# Daughter_Board_V2.net
KiCad netlist of a schematic drawn in EAGLE
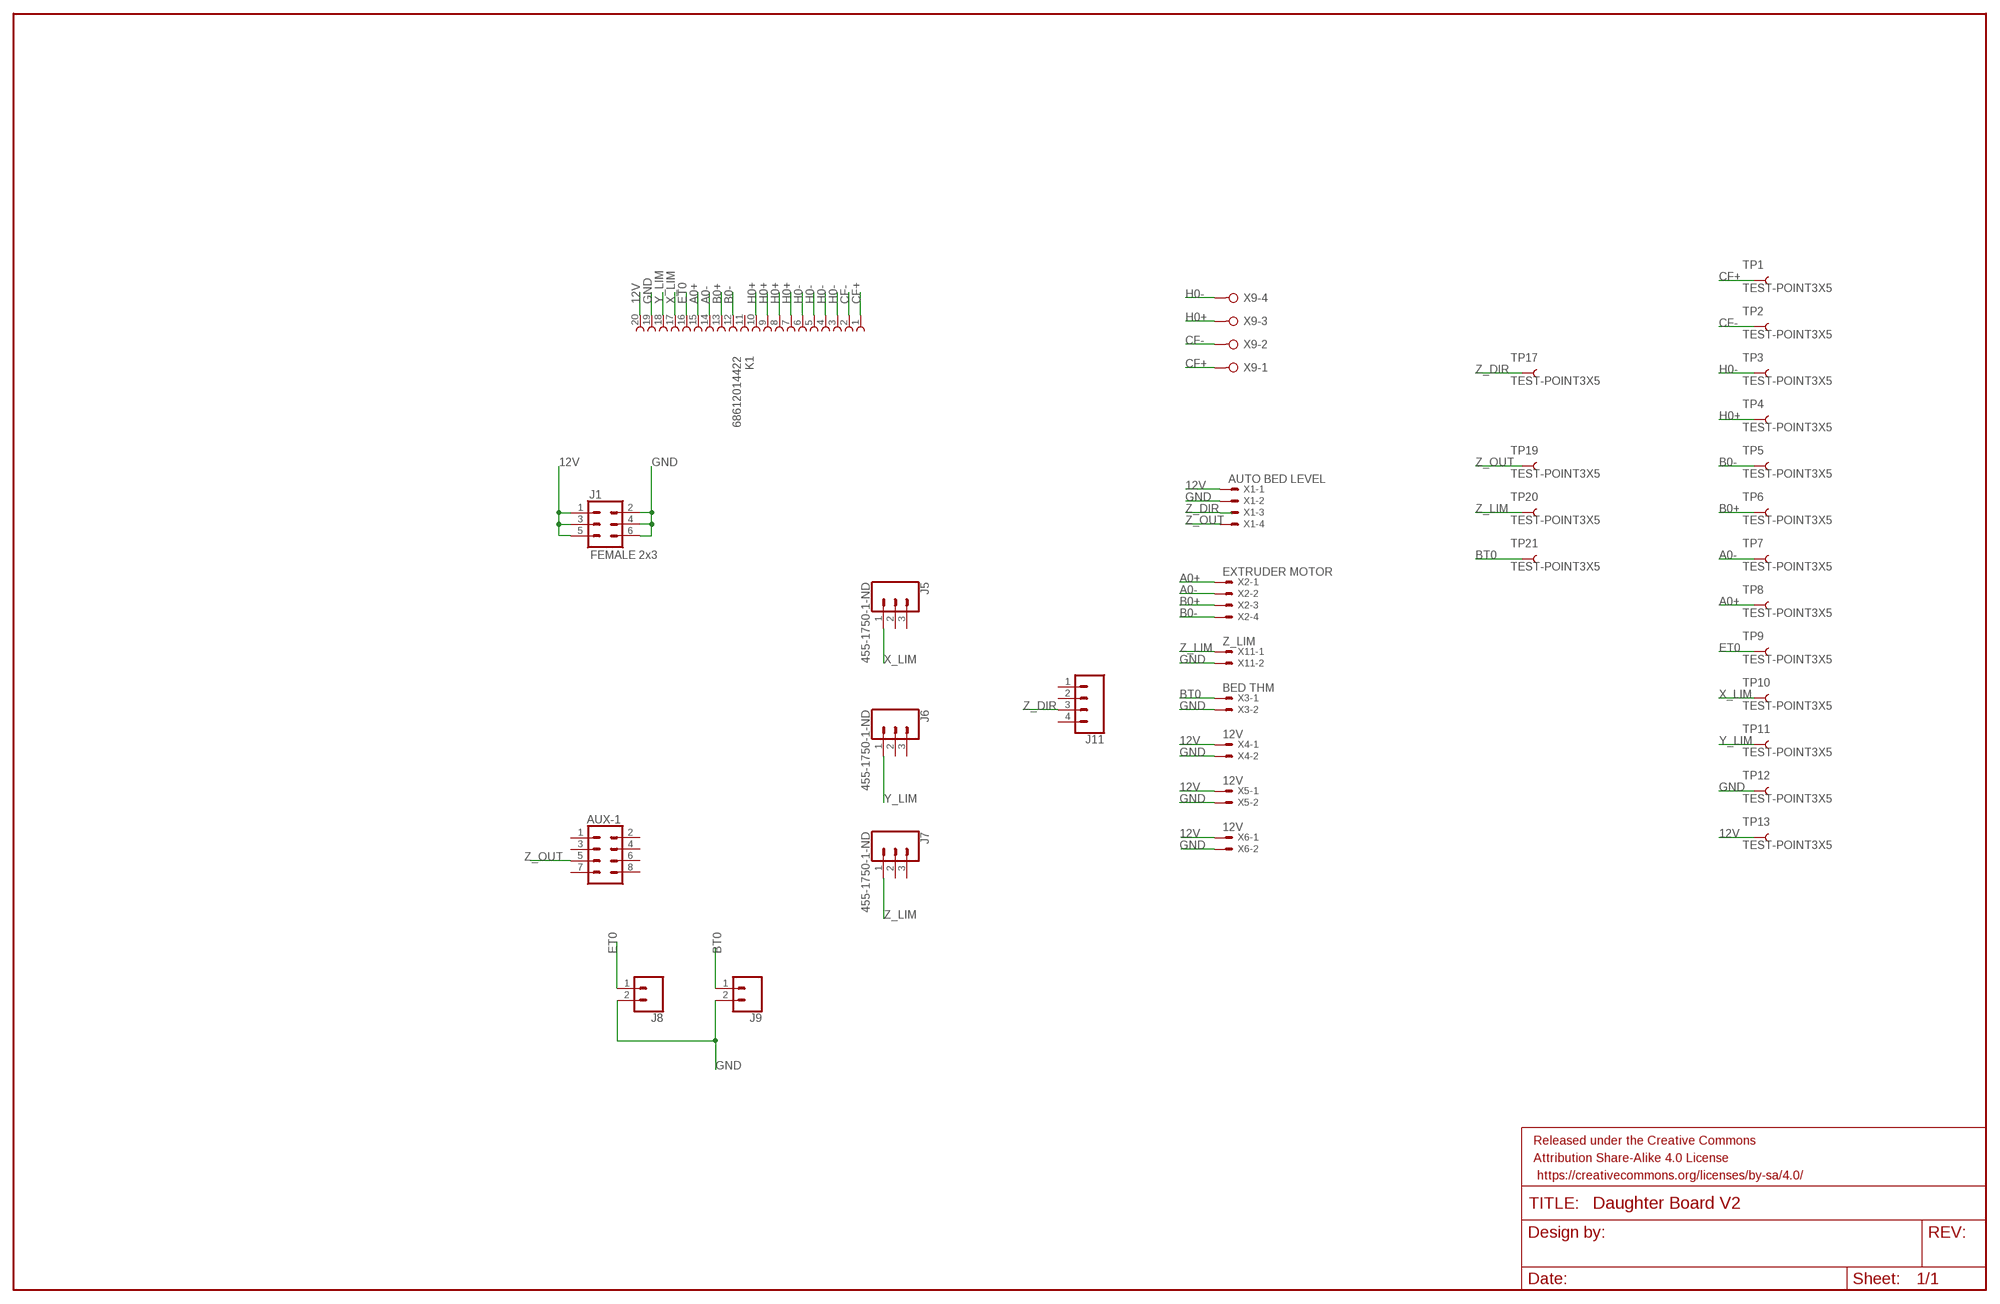
[diagram p0: schematic, sheet 1]

(export (version "E")
  (design (tool "Eeschema 10.0.6"))
  (components
    (comp (ref "AUX-1")
      (value "CONN_04X2")
      (footprint "eagle-import:2X4")
      (libsource (lib "eagle-import") (part "CONN_04X2"))
    )
    (comp (ref "FRAME1")
      (value "FRAME-LEDGER")
      (footprint "eagle-import:CREATIVE_COMMONS")
      (libsource (lib "eagle-import") (part "FRAME-LEDGER"))
    )
    (comp (ref "J1")
      (value "FEMALE 2x3")
      (footprint "eagle-import:2X3")
      (libsource (lib "eagle-import") (part "CONN_03X2FEMALE"))
    )
    (comp (ref "J5")
      (value "455-1750-1-ND")
      (footprint "eagle-import:1X03")
      (libsource (lib "eagle-import") (part "CONN_03"))
    )
    (comp (ref "J6")
      (value "455-1750-1-ND")
      (footprint "eagle-import:1X03")
      (libsource (lib "eagle-import") (part "CONN_03"))
    )
    (comp (ref "J7")
      (value "455-1750-1-ND")
      (footprint "eagle-import:1X03")
      (libsource (lib "eagle-import") (part "CONN_03"))
    )
    (comp (ref "J8")
      (value "CONN_02")
      (footprint "eagle-import:1X02")
      (libsource (lib "eagle-import") (part "CONN_02"))
    )
    (comp (ref "J9")
      (value "CONN_02")
      (footprint "eagle-import:1X02")
      (libsource (lib "eagle-import") (part "CONN_02"))
    )
    (comp (ref "J11")
      (value "CONN_04")
      (footprint "eagle-import:1X04")
      (libsource (lib "eagle-import") (part "CONN_04"))
    )
    (comp (ref "K1")
      (value "68612014422")
      (footprint "eagle-import:68612014422")
      (libsource (lib "eagle-import") (part "68612014422"))
    )
    (comp (ref "TP1")
      (value "TEST-POINT3X5")
      (footprint "eagle-import:PAD.03X.05")
      (libsource (lib "eagle-import") (part "TEST-POINT3X5"))
    )
    (comp (ref "TP2")
      (value "TEST-POINT3X5")
      (footprint "eagle-import:PAD.03X.05")
      (libsource (lib "eagle-import") (part "TEST-POINT3X5"))
    )
    (comp (ref "TP3")
      (value "TEST-POINT3X5")
      (footprint "eagle-import:PAD.03X.05")
      (libsource (lib "eagle-import") (part "TEST-POINT3X5"))
    )
    (comp (ref "TP4")
      (value "TEST-POINT3X5")
      (footprint "eagle-import:PAD.03X.05")
      (libsource (lib "eagle-import") (part "TEST-POINT3X5"))
    )
    (comp (ref "TP5")
      (value "TEST-POINT3X5")
      (footprint "eagle-import:PAD.03X.05")
      (libsource (lib "eagle-import") (part "TEST-POINT3X5"))
    )
    (comp (ref "TP6")
      (value "TEST-POINT3X5")
      (footprint "eagle-import:PAD.03X.05")
      (libsource (lib "eagle-import") (part "TEST-POINT3X5"))
    )
    (comp (ref "TP7")
      (value "TEST-POINT3X5")
      (footprint "eagle-import:PAD.03X.05")
      (libsource (lib "eagle-import") (part "TEST-POINT3X5"))
    )
    (comp (ref "TP8")
      (value "TEST-POINT3X5")
      (footprint "eagle-import:PAD.03X.05")
      (libsource (lib "eagle-import") (part "TEST-POINT3X5"))
    )
    (comp (ref "TP9")
      (value "TEST-POINT3X5")
      (footprint "eagle-import:PAD.03X.05")
      (libsource (lib "eagle-import") (part "TEST-POINT3X5"))
    )
    (comp (ref "TP10")
      (value "TEST-POINT3X5")
      (footprint "eagle-import:PAD.03X.05")
      (libsource (lib "eagle-import") (part "TEST-POINT3X5"))
    )
    (comp (ref "TP11")
      (value "TEST-POINT3X5")
      (footprint "eagle-import:PAD.03X.05")
      (libsource (lib "eagle-import") (part "TEST-POINT3X5"))
    )
    (comp (ref "TP12")
      (value "TEST-POINT3X5")
      (footprint "eagle-import:PAD.03X.05")
      (libsource (lib "eagle-import") (part "TEST-POINT3X5"))
    )
    (comp (ref "TP13")
      (value "TEST-POINT3X5")
      (footprint "eagle-import:PAD.03X.05")
      (libsource (lib "eagle-import") (part "TEST-POINT3X5"))
    )
    (comp (ref "TP17")
      (value "TEST-POINT3X5")
      (footprint "eagle-import:PAD.03X.05")
      (libsource (lib "eagle-import") (part "TEST-POINT3X5"))
    )
    (comp (ref "TP19")
      (value "TEST-POINT3X5")
      (footprint "eagle-import:PAD.03X.05")
      (libsource (lib "eagle-import") (part "TEST-POINT3X5"))
    )
    (comp (ref "TP20")
      (value "TEST-POINT3X5")
      (footprint "eagle-import:PAD.03X.05")
      (libsource (lib "eagle-import") (part "TEST-POINT3X5"))
    )
    (comp (ref "TP21")
      (value "TEST-POINT3X5")
      (footprint "eagle-import:PAD.03X.05")
      (libsource (lib "eagle-import") (part "TEST-POINT3X5"))
    )
    (comp (ref "X1")
      (value "AUTO BED LEVEL")
      (footprint "eagle-import:JST-XH-04-PACKAGE-LONG-PAD")
      (libsource (lib "eagle-import") (part "JST-XH-04-PIN-LONG-PAD"))
    )
    (comp (ref "X2")
      (value "EXTRUDER MOTOR")
      (footprint "eagle-import:JST-XH-04-PACKAGE-LONG-PAD")
      (libsource (lib "eagle-import") (part "JST-XH-04-PIN-LONG-PAD"))
    )
    (comp (ref "X3")
      (value "BED THM")
      (footprint "eagle-import:JST-XH-02-PACKAGE-LONG-PAD")
      (libsource (lib "eagle-import") (part "JST-XH-02-PIN-LONG-PAD"))
    )
    (comp (ref "X4")
      (value "12V")
      (footprint "eagle-import:JST-XH-02-PACKAGE-LONG-PAD")
      (libsource (lib "eagle-import") (part "JST-XH-02-PIN-LONG-PAD"))
    )
    (comp (ref "X5")
      (value "12V")
      (footprint "eagle-import:JST-XH-02-PACKAGE-LONG-PAD")
      (libsource (lib "eagle-import") (part "JST-XH-02-PIN-LONG-PAD"))
    )
    (comp (ref "X6")
      (value "12V")
      (footprint "eagle-import:JST-XH-02-PACKAGE-LONG-PAD")
      (libsource (lib "eagle-import") (part "JST-XH-02-PIN-LONG-PAD"))
    )
    (comp (ref "X9")
      (value "W237-04P")
      (footprint "eagle-import:W237-4P")
      (libsource (lib "eagle-import") (part "W237-04P"))
    )
    (comp (ref "X11")
      (value "Z_LIM")
      (footprint "eagle-import:JST-XH-02-PACKAGE-LONG-PAD")
      (libsource (lib "eagle-import") (part "JST-XH-02-PIN-LONG-PAD"))
    )
  )
  (nets
    (net (code "1") (name "/12V") (class "Default")
      (node (ref "J1") (pin "1") (pinfunction "1_1") (pintype "bidirectional"))
      (node (ref "J1") (pin "3") (pinfunction "3_3") (pintype "bidirectional"))
      (node (ref "J1") (pin "5") (pinfunction "5_5") (pintype "bidirectional"))
      (node (ref "K1") (pin "20") (pinfunction "20_20") (pintype "passive"))
      (node (ref "TP13") (pin "P$1") (pinfunction "1_P$1") (pintype "bidirectional"))
      (node (ref "X1") (pin "1") (pinfunction "S_1") (pintype "passive"))
      (node (ref "X4") (pin "1") (pinfunction "S_1") (pintype "passive"))
      (node (ref "X5") (pin "1") (pinfunction "S_1") (pintype "passive"))
      (node (ref "X6") (pin "1") (pinfunction "S_1") (pintype "passive"))
    )
    (net (code "2") (name "/A0+") (class "Default")
      (node (ref "K1") (pin "15") (pinfunction "15_15") (pintype "passive"))
      (node (ref "TP8") (pin "P$1") (pinfunction "1_P$1") (pintype "bidirectional"))
      (node (ref "X2") (pin "1") (pinfunction "S_1") (pintype "passive"))
    )
    (net (code "3") (name "/A0-") (class "Default")
      (node (ref "K1") (pin "14") (pinfunction "14_14") (pintype "passive"))
      (node (ref "TP7") (pin "P$1") (pinfunction "1_P$1") (pintype "bidirectional"))
      (node (ref "X2") (pin "2") (pinfunction "S_2") (pintype "passive"))
    )
    (net (code "4") (name "/B0+") (class "Default")
      (node (ref "K1") (pin "13") (pinfunction "13_13") (pintype "passive"))
      (node (ref "TP6") (pin "P$1") (pinfunction "1_P$1") (pintype "bidirectional"))
      (node (ref "X2") (pin "3") (pinfunction "S_3") (pintype "passive"))
    )
    (net (code "5") (name "/B0-") (class "Default")
      (node (ref "K1") (pin "12") (pinfunction "12_12") (pintype "passive"))
      (node (ref "TP5") (pin "P$1") (pinfunction "1_P$1") (pintype "bidirectional"))
      (node (ref "X2") (pin "4") (pinfunction "S_4") (pintype "passive"))
    )
    (net (code "6") (name "/BT0") (class "Default")
      (node (ref "J9") (pin "1") (pinfunction "1_1") (pintype "passive"))
      (node (ref "TP21") (pin "P$1") (pinfunction "1_P$1") (pintype "bidirectional"))
      (node (ref "X3") (pin "1") (pinfunction "S_1") (pintype "passive"))
    )
    (net (code "7") (name "/CF+") (class "Default")
      (node (ref "K1") (pin "1") (pinfunction "1_1") (pintype "passive"))
      (node (ref "TP1") (pin "P$1") (pinfunction "1_P$1") (pintype "bidirectional"))
      (node (ref "X9") (pin "1") (pinfunction "KL_1") (pintype "passive"))
    )
    (net (code "8") (name "/CF-") (class "Default")
      (node (ref "K1") (pin "2") (pinfunction "2_2") (pintype "passive"))
      (node (ref "TP2") (pin "P$1") (pinfunction "1_P$1") (pintype "bidirectional"))
      (node (ref "X9") (pin "2") (pinfunction "KL_2") (pintype "passive"))
    )
    (net (code "9") (name "/ET0") (class "Default")
      (node (ref "J8") (pin "1") (pinfunction "1_1") (pintype "passive"))
      (node (ref "K1") (pin "16") (pinfunction "16_16") (pintype "passive"))
      (node (ref "TP9") (pin "P$1") (pinfunction "1_P$1") (pintype "bidirectional"))
    )
    (net (code "10") (name "/GND") (class "Default")
      (node (ref "J1") (pin "2") (pinfunction "2_2") (pintype "bidirectional"))
      (node (ref "J1") (pin "4") (pinfunction "4_4") (pintype "bidirectional"))
      (node (ref "J1") (pin "6") (pinfunction "6_6") (pintype "bidirectional"))
      (node (ref "J8") (pin "2") (pinfunction "2_2") (pintype "passive"))
      (node (ref "J9") (pin "2") (pinfunction "2_2") (pintype "passive"))
      (node (ref "K1") (pin "19") (pinfunction "19_19") (pintype "passive"))
      (node (ref "TP12") (pin "P$1") (pinfunction "1_P$1") (pintype "bidirectional"))
      (node (ref "X1") (pin "2") (pinfunction "S_2") (pintype "passive"))
      (node (ref "X11") (pin "2") (pinfunction "S_2") (pintype "passive"))
      (node (ref "X3") (pin "2") (pinfunction "S_2") (pintype "passive"))
      (node (ref "X4") (pin "2") (pinfunction "S_2") (pintype "passive"))
      (node (ref "X5") (pin "2") (pinfunction "S_2") (pintype "passive"))
      (node (ref "X6") (pin "2") (pinfunction "S_2") (pintype "passive"))
    )
    (net (code "11") (name "/H0+") (class "Default")
      (node (ref "K1") (pin "10") (pinfunction "10_10") (pintype "passive"))
      (node (ref "K1") (pin "7") (pinfunction "7_7") (pintype "passive"))
      (node (ref "K1") (pin "8") (pinfunction "8_8") (pintype "passive"))
      (node (ref "K1") (pin "9") (pinfunction "9_9") (pintype "passive"))
      (node (ref "TP4") (pin "P$1") (pinfunction "1_P$1") (pintype "bidirectional"))
      (node (ref "X9") (pin "3") (pinfunction "KL_3") (pintype "passive"))
    )
    (net (code "12") (name "/H0-") (class "Default")
      (node (ref "K1") (pin "3") (pinfunction "3_3") (pintype "passive"))
      (node (ref "K1") (pin "4") (pinfunction "4_4") (pintype "passive"))
      (node (ref "K1") (pin "5") (pinfunction "5_5") (pintype "passive"))
      (node (ref "K1") (pin "6") (pinfunction "6_6") (pintype "passive"))
      (node (ref "TP3") (pin "P$1") (pinfunction "1_P$1") (pintype "bidirectional"))
      (node (ref "X9") (pin "4") (pinfunction "KL_4") (pintype "passive"))
    )
    (net (code "13") (name "/X_LIM") (class "Default")
      (node (ref "J5") (pin "1") (pinfunction "1_1") (pintype "passive"))
      (node (ref "K1") (pin "17") (pinfunction "17_17") (pintype "passive"))
      (node (ref "TP10") (pin "P$1") (pinfunction "1_P$1") (pintype "bidirectional"))
    )
    (net (code "14") (name "/Y_LIM") (class "Default")
      (node (ref "J6") (pin "1") (pinfunction "1_1") (pintype "passive"))
      (node (ref "K1") (pin "18") (pinfunction "18_18") (pintype "passive"))
      (node (ref "TP11") (pin "P$1") (pinfunction "1_P$1") (pintype "bidirectional"))
    )
    (net (code "15") (name "/Z_DIR") (class "Default")
      (node (ref "J11") (pin "3") (pinfunction "3_3") (pintype "passive"))
      (node (ref "TP17") (pin "P$1") (pinfunction "1_P$1") (pintype "bidirectional"))
      (node (ref "X1") (pin "3") (pinfunction "S_3") (pintype "passive"))
    )
    (net (code "16") (name "/Z_LIM") (class "Default")
      (node (ref "J7") (pin "1") (pinfunction "1_1") (pintype "passive"))
      (node (ref "TP20") (pin "P$1") (pinfunction "1_P$1") (pintype "bidirectional"))
      (node (ref "X11") (pin "1") (pinfunction "S_1") (pintype "passive"))
    )
    (net (code "17") (name "/Z_OUT") (class "Default")
      (node (ref "AUX-1") (pin "5") (pinfunction "5_5") (pintype "passive"))
      (node (ref "TP19") (pin "P$1") (pinfunction "1_P$1") (pintype "bidirectional"))
      (node (ref "X1") (pin "4") (pinfunction "S_4") (pintype "passive"))
    )
    (net (code "18") (name "unconnected-(AUX-1-Pad1)") (class "Default")
      (node (ref "AUX-1") (pin "1") (pinfunction "1_1") (pintype "passive"))
    )
    (net (code "19") (name "unconnected-(AUX-1-Pad2)") (class "Default")
      (node (ref "AUX-1") (pin "2") (pinfunction "2_2") (pintype "passive"))
    )
    (net (code "20") (name "unconnected-(AUX-1-Pad3)") (class "Default")
      (node (ref "AUX-1") (pin "3") (pinfunction "3_3") (pintype "passive"))
    )
    (net (code "21") (name "unconnected-(AUX-1-Pad4)") (class "Default")
      (node (ref "AUX-1") (pin "4") (pinfunction "4_4") (pintype "passive"))
    )
    (net (code "22") (name "unconnected-(AUX-1-Pad6)") (class "Default")
      (node (ref "AUX-1") (pin "6") (pinfunction "6_6") (pintype "passive"))
    )
    (net (code "23") (name "unconnected-(AUX-1-Pad7)") (class "Default")
      (node (ref "AUX-1") (pin "7") (pinfunction "7_7") (pintype "passive"))
    )
    (net (code "24") (name "unconnected-(AUX-1-Pad8)") (class "Default")
      (node (ref "AUX-1") (pin "8") (pinfunction "8_8") (pintype "passive"))
    )
    (net (code "25") (name "unconnected-(J5-Pad2)") (class "Default")
      (node (ref "J5") (pin "2") (pinfunction "2_2") (pintype "passive"))
    )
    (net (code "26") (name "unconnected-(J5-Pad3)") (class "Default")
      (node (ref "J5") (pin "3") (pinfunction "3_3") (pintype "passive"))
    )
    (net (code "27") (name "unconnected-(J6-Pad2)") (class "Default")
      (node (ref "J6") (pin "2") (pinfunction "2_2") (pintype "passive"))
    )
    (net (code "28") (name "unconnected-(J6-Pad3)") (class "Default")
      (node (ref "J6") (pin "3") (pinfunction "3_3") (pintype "passive"))
    )
    (net (code "29") (name "unconnected-(J7-Pad2)") (class "Default")
      (node (ref "J7") (pin "2") (pinfunction "2_2") (pintype "passive"))
    )
    (net (code "30") (name "unconnected-(J7-Pad3)") (class "Default")
      (node (ref "J7") (pin "3") (pinfunction "3_3") (pintype "passive"))
    )
    (net (code "31") (name "unconnected-(J11-Pad1)") (class "Default")
      (node (ref "J11") (pin "1") (pinfunction "1_1") (pintype "passive"))
    )
    (net (code "32") (name "unconnected-(J11-Pad2)") (class "Default")
      (node (ref "J11") (pin "2") (pinfunction "2_2") (pintype "passive"))
    )
    (net (code "33") (name "unconnected-(J11-Pad4)") (class "Default")
      (node (ref "J11") (pin "4") (pinfunction "4_4") (pintype "passive"))
    )
    (net (code "34") (name "unconnected-(K1-Pad11)") (class "Default")
      (node (ref "K1") (pin "11") (pinfunction "11_11") (pintype "passive"))
    )
  )
)
